# Rev3.net
KiCad netlist of a schematic drawn in EAGLE
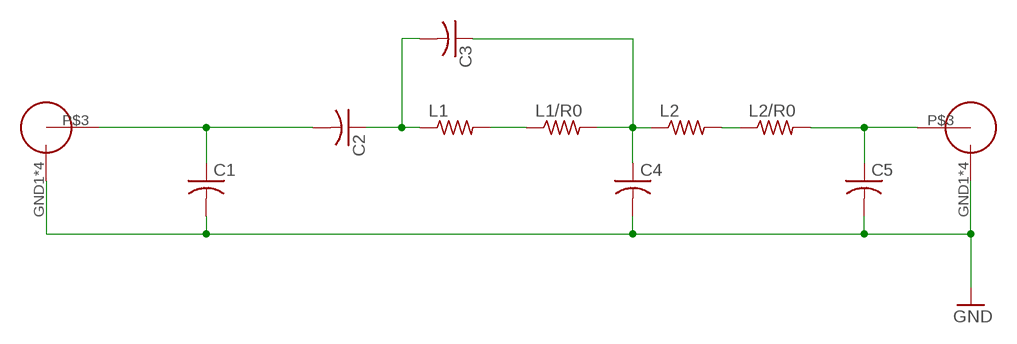
[diagram p0: schematic, sheet 1]

(export (version "E")
  (design (tool "Eeschema 10.0.6"))
  (components
    (comp (ref "C1")
      (value "C-USC0603")
      (footprint "eagle-import:C0603")
      (libsource (lib "eagle-import") (part "C-USC0603"))
    )
    (comp (ref "C2")
      (value "C-USC0603")
      (footprint "eagle-import:C0603")
      (libsource (lib "eagle-import") (part "C-USC0603"))
    )
    (comp (ref "C3")
      (value "C-USC0603")
      (footprint "eagle-import:C0603")
      (libsource (lib "eagle-import") (part "C-USC0603"))
    )
    (comp (ref "C4")
      (value "C-USC0603")
      (footprint "eagle-import:C0603")
      (libsource (lib "eagle-import") (part "C-USC0603"))
    )
    (comp (ref "C5")
      (value "C-USC0603")
      (footprint "eagle-import:C0603")
      (libsource (lib "eagle-import") (part "C-USC0603"))
    )
    (comp (ref "L1")
      (value "R-US_R0603")
      (footprint "eagle-import:R0603")
      (libsource (lib "eagle-import") (part "R-US_R0603"))
    )
    (comp (ref "L1/R0")
      (value "R-US_R0603")
      (footprint "eagle-import:R0603")
      (libsource (lib "eagle-import") (part "R-US_R0603"))
    )
    (comp (ref "L2")
      (value "R-US_R0603")
      (footprint "eagle-import:R0603")
      (libsource (lib "eagle-import") (part "R-US_R0603"))
    )
    (comp (ref "L2/R0")
      (value "R-US_R0603")
      (footprint "eagle-import:R0603")
      (libsource (lib "eagle-import") (part "R-US_R0603"))
    )
    (comp (ref "U$1")
      (value "SMAJ716-ND")
      (footprint "eagle-import:SMAJ716-ND")
      (libsource (lib "eagle-import") (part "SMAJ716-ND"))
    )
    (comp (ref "U$2")
      (value "SMAJ716-ND")
      (footprint "eagle-import:SMAJ716-ND")
      (libsource (lib "eagle-import") (part "SMAJ716-ND"))
    )
  )
  (nets
    (net (code "1") (name "GND") (class "Default")
      (node (ref "C1") (pin "2") (pinfunction "2_2") (pintype "passive"))
      (node (ref "C4") (pin "2") (pinfunction "2_2") (pintype "passive"))
      (node (ref "C5") (pin "2") (pinfunction "2_2") (pintype "passive"))
      (node (ref "U$1") (pin "GND1") (pinfunction "OUTERCONDUCTOR_GND1") (pintype "bidirectional"))
      (node (ref "U$1") (pin "GND2") (pinfunction "OUTERCONDUCTOR_GND2") (pintype "bidirectional"))
      (node (ref "U$1") (pin "GND3") (pinfunction "OUTERCONDUCTOR_GND3") (pintype "bidirectional"))
      (node (ref "U$1") (pin "GND4") (pinfunction "OUTERCONDUCTOR_GND4") (pintype "bidirectional"))
      (node (ref "U$2") (pin "GND1") (pinfunction "OUTERCONDUCTOR_GND1") (pintype "bidirectional"))
      (node (ref "U$2") (pin "GND2") (pinfunction "OUTERCONDUCTOR_GND2") (pintype "bidirectional"))
      (node (ref "U$2") (pin "GND3") (pinfunction "OUTERCONDUCTOR_GND3") (pintype "bidirectional"))
      (node (ref "U$2") (pin "GND4") (pinfunction "OUTERCONDUCTOR_GND4") (pintype "bidirectional"))
    )
    (net (code "2") (name "Net-(C2-Pad1)") (class "Default")
      (node (ref "C2") (pin "1") (pinfunction "1_1") (pintype "passive"))
      (node (ref "C3") (pin "2") (pinfunction "2_2") (pintype "passive"))
      (node (ref "L1") (pin "1") (pinfunction "1_1") (pintype "passive"))
    )
    (net (code "3") (name "Net-(C3-Pad1)") (class "Default")
      (node (ref "C3") (pin "1") (pinfunction "1_1") (pintype "passive"))
      (node (ref "C4") (pin "1") (pinfunction "1_1") (pintype "passive"))
      (node (ref "L1/R0") (pin "2") (pinfunction "2_2") (pintype "passive"))
      (node (ref "L2") (pin "1") (pinfunction "1_1") (pintype "passive"))
    )
    (net (code "4") (name "Net-(L1-Pad2)") (class "Default")
      (node (ref "L1") (pin "2") (pinfunction "2_2") (pintype "passive"))
      (node (ref "L1/R0") (pin "1") (pinfunction "1_1") (pintype "passive"))
    )
    (net (code "5") (name "Net-(L2-Pad2)") (class "Default")
      (node (ref "L2") (pin "2") (pinfunction "2_2") (pintype "passive"))
      (node (ref "L2/R0") (pin "1") (pinfunction "1_1") (pintype "passive"))
    )
    (net (code "6") (name "Net-(U$1-CENTERCONDUCTOR)") (class "Default")
      (node (ref "C1") (pin "1") (pinfunction "1_1") (pintype "passive"))
      (node (ref "C2") (pin "2") (pinfunction "2_2") (pintype "passive"))
      (node (ref "U$1") (pin "P$3") (pinfunction "CENTERCONDUCTOR_P$3") (pintype "bidirectional"))
    )
    (net (code "7") (name "Net-(U$2-CENTERCONDUCTOR)") (class "Default")
      (node (ref "C5") (pin "1") (pinfunction "1_1") (pintype "passive"))
      (node (ref "L2/R0") (pin "2") (pinfunction "2_2") (pintype "passive"))
      (node (ref "U$2") (pin "P$3") (pinfunction "CENTERCONDUCTOR_P$3") (pintype "bidirectional"))
    )
  )
)
